# ProPrj__NFC__2025-08-22.net
KiCad netlist of a schematic drawn in EasyEDA Pro
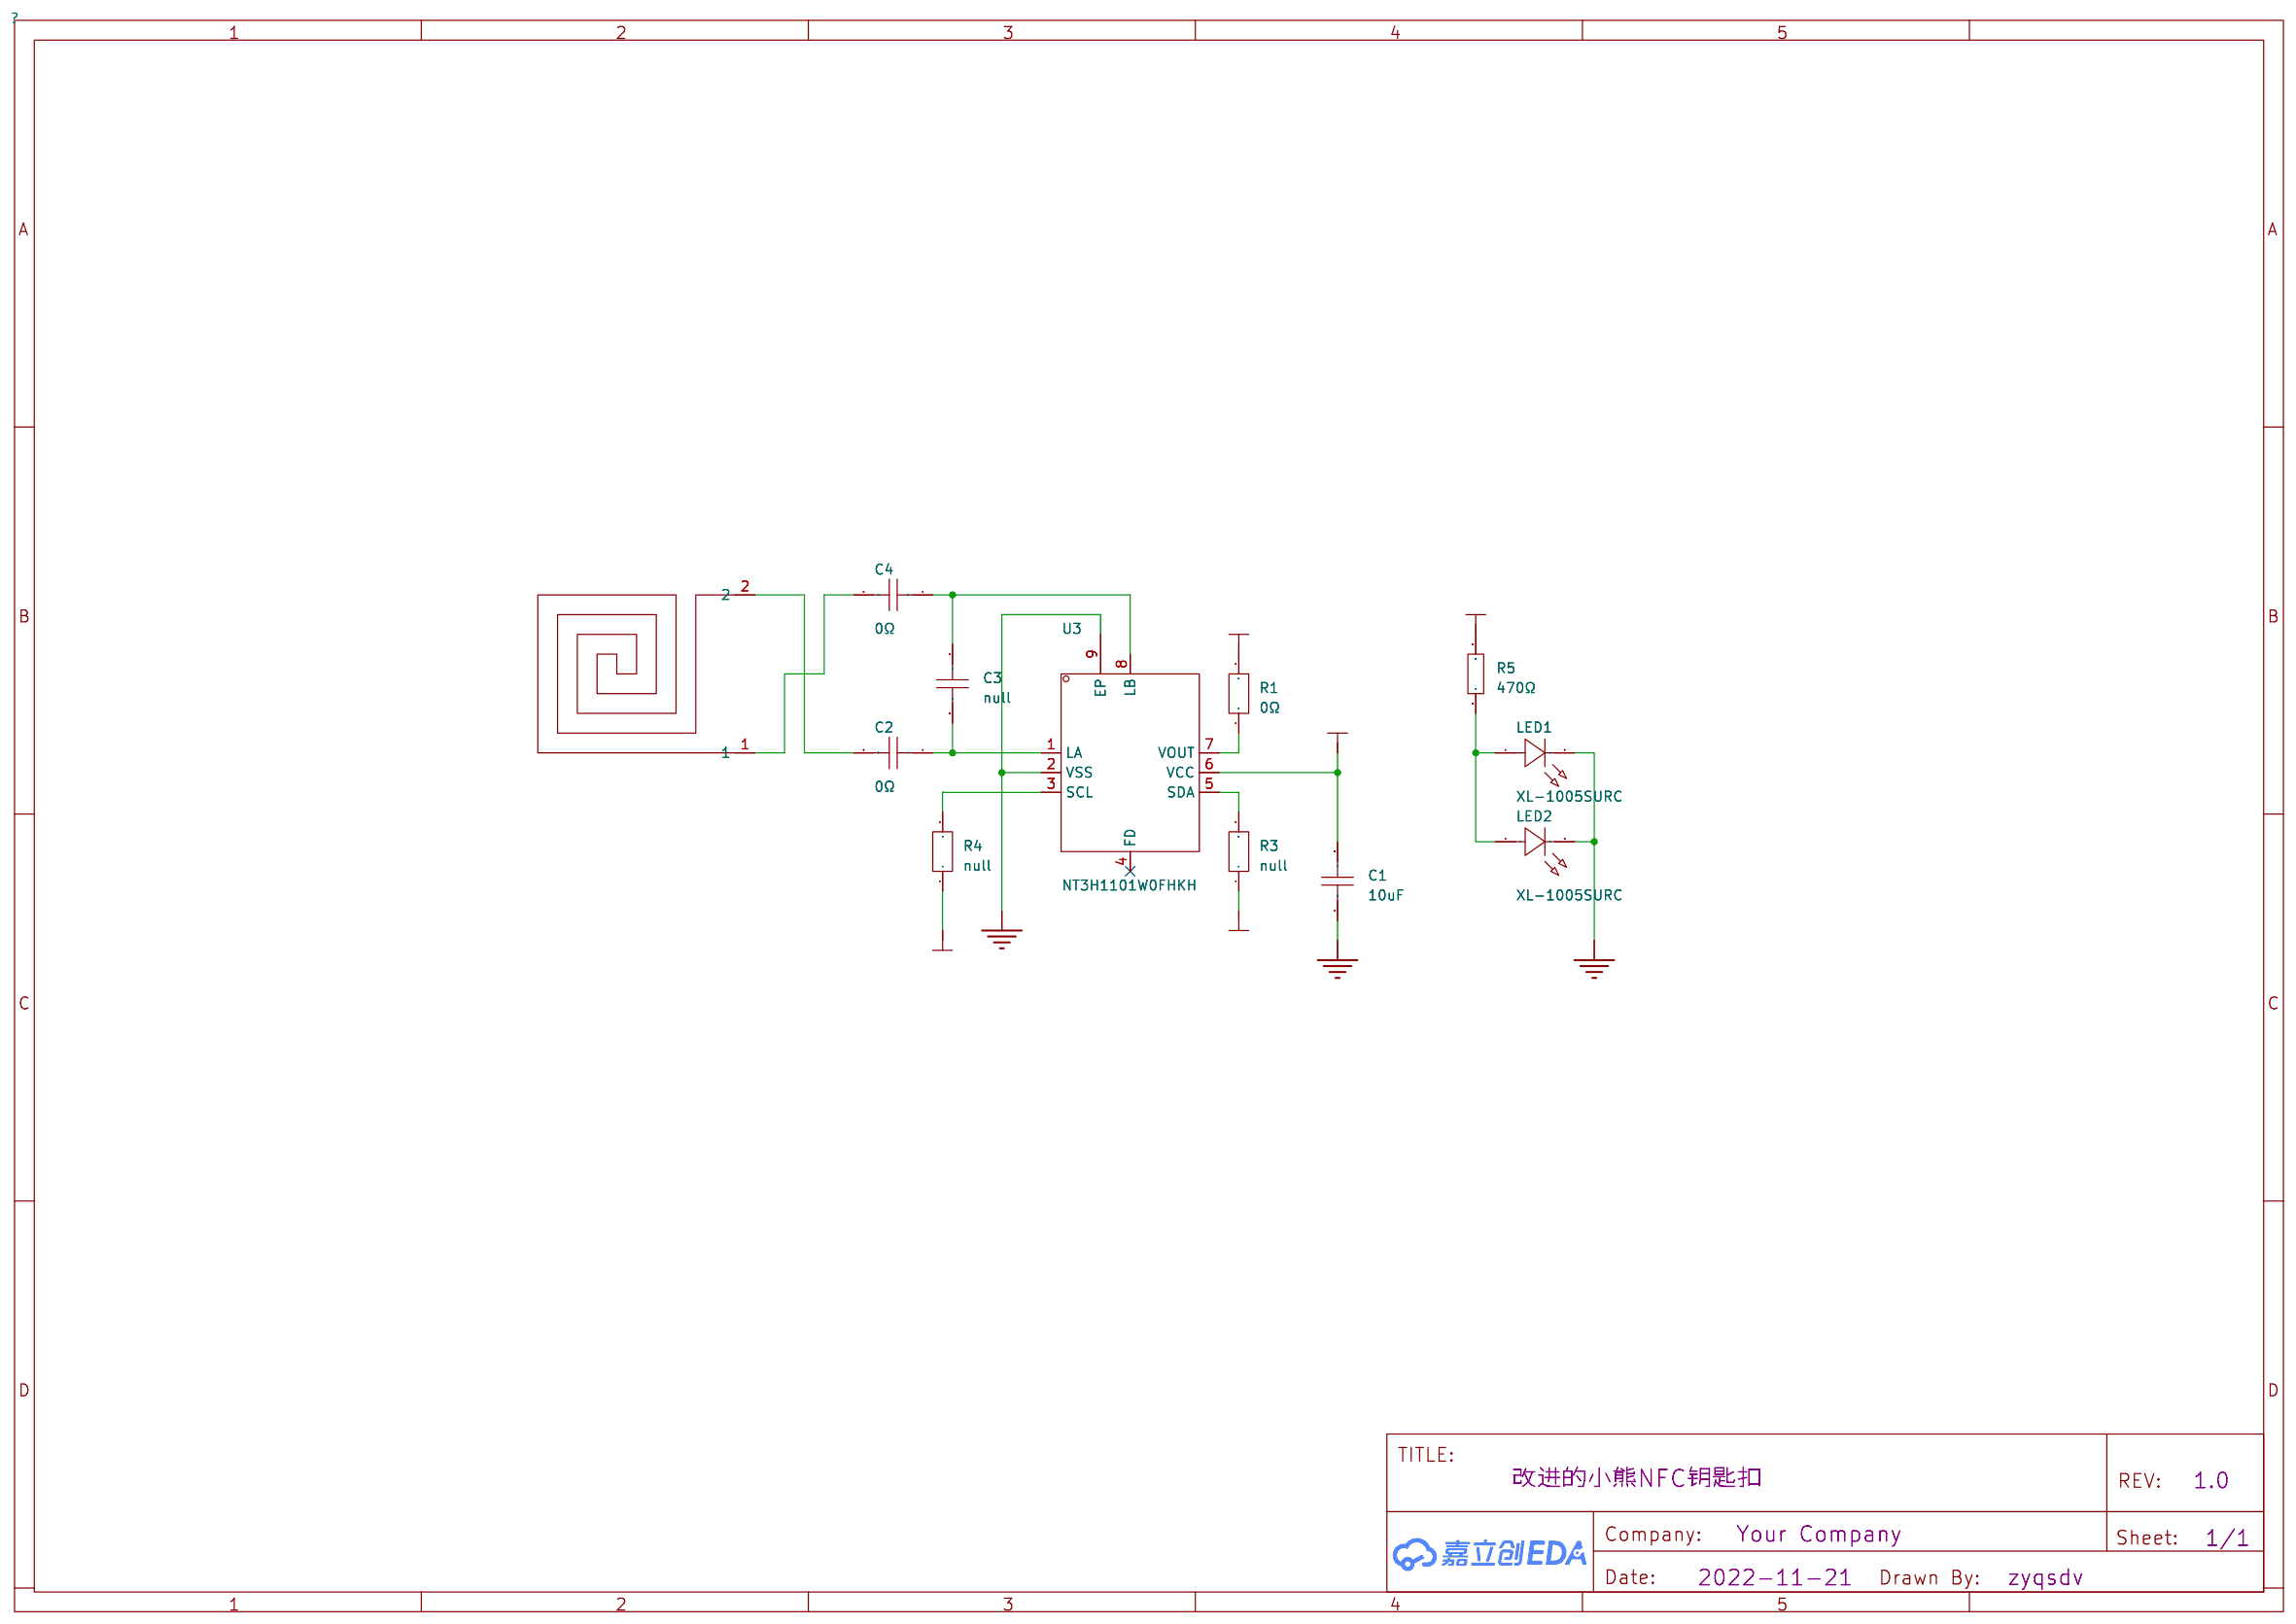
[diagram p0: schematic sheet]

(export (version "E")
  (design (tool "Eeschema 10.0.6"))
  (components
    (comp (ref "A1")
      (value "~")
      (footprint "easyedapro:2825NFCAnt")
      (libsource (lib "easyedapro") (part "NFCAnt"))
    )
    (comp (ref "C1")
      (value "10uF")
      (footprint "easyedapro:C0402")
      (description "容值:100nF;精度:±10%;额定电压:16V;材质(温度系数):X7R;")
      (fields
        (field (name "Manufacturer Part") "CC0402KRX7R7BB104")
        (field (name "Manufacturer") "YAGEO(国巨)")
      )
      (libsource (lib "easyedapro") (part "CC0402KRX7R7BB104"))
    )
    (comp (ref "C2")
      (value "0Ω")
      (footprint "easyedapro:C0402")
      (description "容值:100nF;精度:±10%;额定电压:16V;材质(温度系数):X7R;")
      (fields
        (field (name "Manufacturer Part") "CC0402KRX7R7BB104")
        (field (name "Manufacturer") "YAGEO(国巨)")
      )
      (libsource (lib "easyedapro") (part "CC0402KRX7R7BB104"))
    )
    (comp (ref "C3")
      (value "null")
      (footprint "easyedapro:C0402")
      (description "容值:100nF;精度:±10%;额定电压:16V;材质(温度系数):X7R;")
      (fields
        (field (name "Manufacturer Part") "CC0402KRX7R7BB104")
        (field (name "Manufacturer") "YAGEO(国巨)")
      )
      (libsource (lib "easyedapro") (part "CC0402KRX7R7BB104"))
    )
    (comp (ref "C4")
      (value "0Ω")
      (footprint "easyedapro:C0402")
      (description "容值:100nF;精度:±10%;额定电压:16V;材质(温度系数):X7R;")
      (fields
        (field (name "Manufacturer Part") "CC0402KRX7R7BB104")
        (field (name "Manufacturer") "YAGEO(国巨)")
      )
      (libsource (lib "easyedapro") (part "CC0402KRX7R7BB104"))
    )
    (comp (ref "LED1")
      (value "XL-1005SURC")
      (footprint "easyedapro:LED0402-R-RD_RED")
      (description "发光颜色:红灯;主波长:620nm;色温:6000K~7000K;功率:55mW;安装方式:正贴;")
      (fields (field (name "Manufacturer") "XINGLIGHT(成兴光)"))
      (libsource (lib "easyedapro") (part "XL-1005SURC"))
    )
    (comp (ref "LED2")
      (value "XL-1005SURC")
      (footprint "easyedapro:LED0402-R-RD_RED")
      (description "发光颜色:红灯;主波长:620nm;色温:6000K~7000K;功率:55mW;安装方式:正贴;")
      (fields (field (name "Manufacturer") "XINGLIGHT(成兴光)"))
      (libsource (lib "easyedapro") (part "XL-1005SURC"))
    )
    (comp (ref "R1")
      (value "0Ω")
      (footprint "easyedapro:R0201")
      (description "阻值:0Ω;精度:±1%;功率:50mW;电阻类型:厚膜电阻;")
      (fields
        (field (name "Manufacturer Part") "0201WMF0000TEE")
        (field (name "Manufacturer") "UNI-ROYAL(厚声)")
      )
      (libsource (lib "easyedapro") (part "0201WMF0000TEE"))
    )
    (comp (ref "R3")
      (value "null")
      (footprint "easyedapro:R0201")
      (description "阻值:0Ω;精度:±1%;功率:50mW;电阻类型:厚膜电阻;")
      (fields
        (field (name "Manufacturer Part") "0201WMF0000TEE")
        (field (name "Manufacturer") "UNI-ROYAL(厚声)")
      )
      (libsource (lib "easyedapro") (part "0201WMF0000TEE"))
    )
    (comp (ref "R4")
      (value "null")
      (footprint "easyedapro:R0201")
      (description "阻值:0Ω;精度:±1%;功率:50mW;电阻类型:厚膜电阻;")
      (fields
        (field (name "Manufacturer Part") "0201WMF0000TEE")
        (field (name "Manufacturer") "UNI-ROYAL(厚声)")
      )
      (libsource (lib "easyedapro") (part "0201WMF0000TEE"))
    )
    (comp (ref "R5")
      (value "470Ω")
      (footprint "easyedapro:R0402")
      (description "阻值:470Ω;精度:±1%;功率:62.5mW;温度系数:±100ppm/°C;电阻类型:厚膜电阻;")
      (fields
        (field (name "Manufacturer Part") "0402WGF4700TCE")
        (field (name "Manufacturer") "UNI-ROYAL(厚声)")
      )
      (libsource (lib "easyedapro") (part "0402WGF4700TCE"))
    )
    (comp (ref "U3")
      (value "NT3H1101W0FHKH")
      (footprint "easyedapro:XQFN-8_L1.6-W1.6-P0.50-BR")
      (fields (field (name "Manufacturer") "NXP(恩智浦)"))
      (libsource (lib "easyedapro") (part "NT3H1101W0FHKH"))
    )
  )
  (nets
    (net (code "1") (name "GND") (class "Default")
      (node (ref "C1") (pin "1") (pinfunction "1_1") (pintype "input"))
      (node (ref "LED1") (pin "2") (pinfunction "A_2") (pintype "input"))
      (node (ref "LED2") (pin "2") (pinfunction "A_2") (pintype "input"))
      (node (ref "U3") (pin "2") (pinfunction "VSS_2") (pintype "input"))
      (node (ref "U3") (pin "9") (pinfunction "EP_9") (pintype "input"))
    )
    (net (code "2") (name "Net-(A1-Pad1)") (class "Default")
      (node (ref "A1") (pin "1") (pinfunction "1_1") (pintype "input"))
      (node (ref "C4") (pin "2") (pinfunction "2_2") (pintype "input"))
    )
    (net (code "3") (name "Net-(A1-Pad2)") (class "Default")
      (node (ref "A1") (pin "2") (pinfunction "2_2") (pintype "input"))
      (node (ref "C2") (pin "2") (pinfunction "2_2") (pintype "input"))
    )
    (net (code "4") (name "Net-(LED1-K)") (class "Default")
      (node (ref "LED1") (pin "1") (pinfunction "K_1") (pintype "input"))
      (node (ref "LED2") (pin "1") (pinfunction "K_1") (pintype "input"))
      (node (ref "R5") (pin "1") (pinfunction "1_1") (pintype "input"))
    )
    (net (code "5") (name "Net-(U3-LA)") (class "Default")
      (node (ref "C2") (pin "1") (pinfunction "1_1") (pintype "input"))
      (node (ref "C3") (pin "2") (pinfunction "2_2") (pintype "input"))
      (node (ref "U3") (pin "1") (pinfunction "LA_1") (pintype "input"))
    )
    (net (code "6") (name "Net-(U3-LB)") (class "Default")
      (node (ref "C3") (pin "1") (pinfunction "1_1") (pintype "input"))
      (node (ref "C4") (pin "1") (pinfunction "1_1") (pintype "input"))
      (node (ref "U3") (pin "8") (pinfunction "LB_8") (pintype "input"))
    )
    (net (code "7") (name "Net-(U3-SCL)") (class "Default")
      (node (ref "R4") (pin "2") (pinfunction "2_2") (pintype "unspecified"))
      (node (ref "U3") (pin "3") (pinfunction "SCL_3") (pintype "input"))
    )
    (net (code "8") (name "Net-(U3-SDA)") (class "Default")
      (node (ref "R3") (pin "2") (pinfunction "2_2") (pintype "unspecified"))
      (node (ref "U3") (pin "5") (pinfunction "SDA_5") (pintype "input"))
    )
    (net (code "9") (name "Net-(U3-VOUT)") (class "Default")
      (node (ref "R1") (pin "1") (pinfunction "1_1") (pintype "unspecified"))
      (node (ref "U3") (pin "7") (pinfunction "VOUT_7") (pintype "input"))
    )
    (net (code "10") (name "VCCRF") (class "Default")
      (node (ref "C1") (pin "2") (pinfunction "2_2") (pintype "input"))
      (node (ref "R1") (pin "2") (pinfunction "2_2") (pintype "unspecified"))
      (node (ref "R3") (pin "1") (pinfunction "1_1") (pintype "unspecified"))
      (node (ref "R4") (pin "1") (pinfunction "1_1") (pintype "unspecified"))
      (node (ref "R5") (pin "2") (pinfunction "2_2") (pintype "input"))
      (node (ref "U3") (pin "6") (pinfunction "VCC_6") (pintype "input"))
    )
    (net (code "11") (name "unconnected-(U3-FD-Pad4)") (class "Default")
      (node (ref "U3") (pin "4") (pinfunction "FD_4") (pintype "input+no_connect"))
    )
  )
)
